# HID2AMI_Deluxe_Rev2_0_0.net
KiCad netlist of a schematic drawn in EAGLE
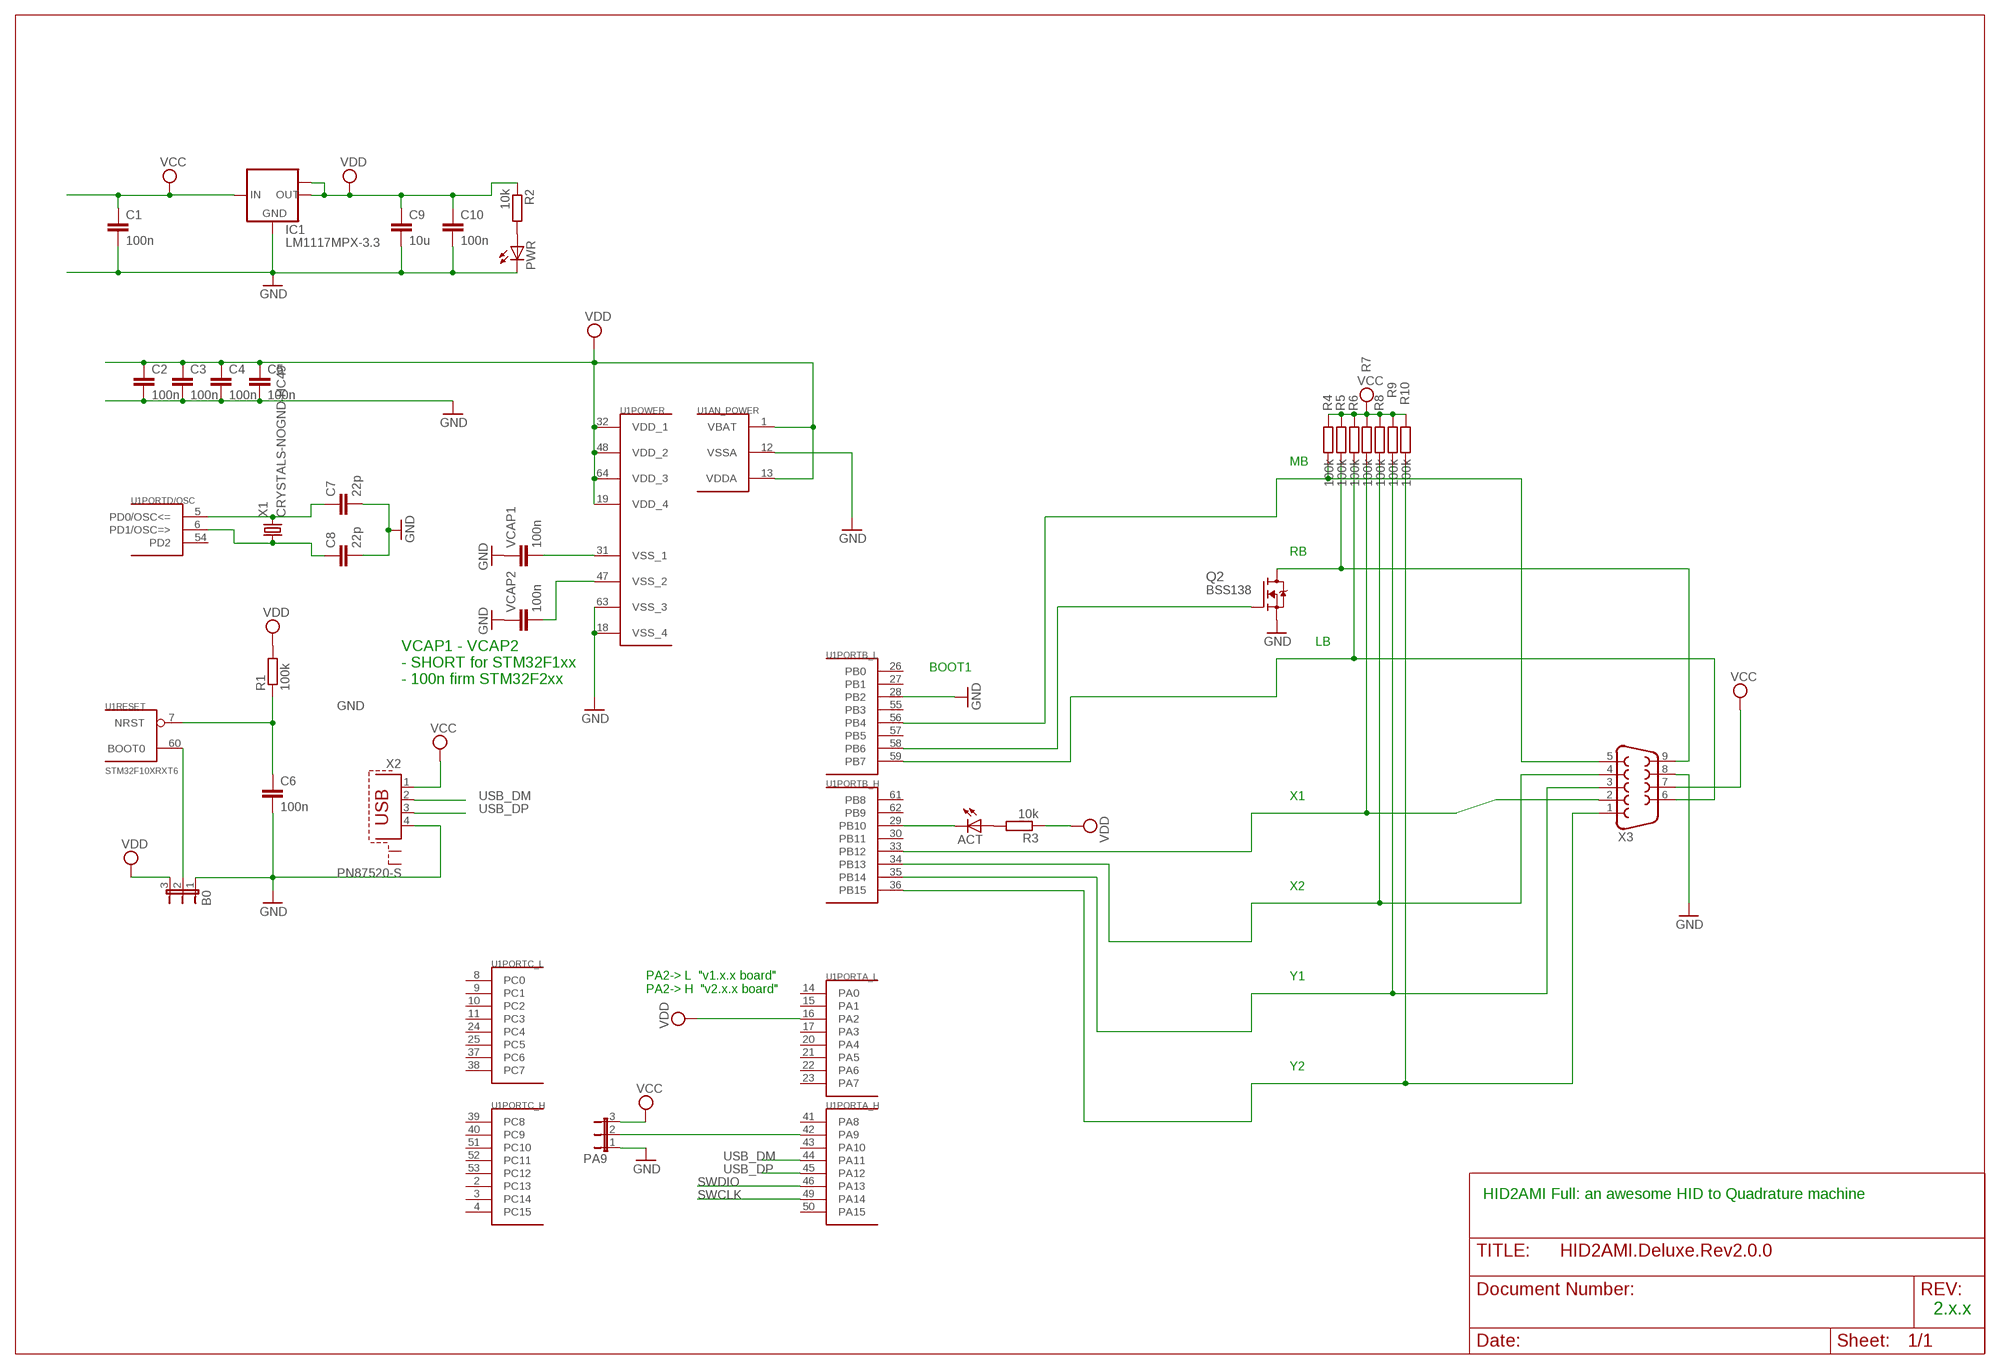
[diagram p0: schematic, sheet 1]

(export (version "E")
  (design (tool "Eeschema 10.0.6"))
  (components
    (comp (ref "ACT")
      (value "LEDSML0805")
      (footprint "eagle-import:SML0805")
      (libsource (lib "eagle-import") (part "LEDSML0805"))
    )
    (comp (ref "B0")
      (value "JP2E")
      (footprint "eagle-import:JP2")
      (libsource (lib "eagle-import") (part "JP2E"))
    )
    (comp (ref "C1")
      (value "100n")
      (footprint "eagle-import:C0805")
      (libsource (lib "eagle-import") (part "C-EUC0805"))
    )
    (comp (ref "C2")
      (value "100n")
      (footprint "eagle-import:C0805")
      (libsource (lib "eagle-import") (part "C-EUC0805"))
    )
    (comp (ref "C3")
      (value "100n")
      (footprint "eagle-import:C0805")
      (libsource (lib "eagle-import") (part "C-EUC0805"))
    )
    (comp (ref "C4")
      (value "100n")
      (footprint "eagle-import:C0805")
      (libsource (lib "eagle-import") (part "C-EUC0805"))
    )
    (comp (ref "C5")
      (value "100n")
      (footprint "eagle-import:C0805")
      (libsource (lib "eagle-import") (part "C-EUC0805"))
    )
    (comp (ref "C6")
      (value "100n")
      (footprint "eagle-import:C0805")
      (libsource (lib "eagle-import") (part "C-EUC0805"))
    )
    (comp (ref "C7")
      (value "22p")
      (footprint "eagle-import:C0805")
      (libsource (lib "eagle-import") (part "C-EUC0805"))
    )
    (comp (ref "C8")
      (value "22p")
      (footprint "eagle-import:C0805")
      (libsource (lib "eagle-import") (part "C-EUC0805"))
    )
    (comp (ref "C9")
      (value "10u")
      (footprint "eagle-import:C0805")
      (libsource (lib "eagle-import") (part "C-EUC0805"))
    )
    (comp (ref "C10")
      (value "100n")
      (footprint "eagle-import:C0805")
      (libsource (lib "eagle-import") (part "C-EUC0805"))
    )
    (comp (ref "IC1")
      (value "LM1117MPX-3.3")
      (footprint "eagle-import:SOT223")
      (libsource (lib "eagle-import") (part "LM1117MPX-3.3"))
    )
    (comp (ref "PA9")
      (value "JP2E")
      (footprint "eagle-import:JP2")
      (libsource (lib "eagle-import") (part "JP2E"))
    )
    (comp (ref "PWR")
      (value "LEDSML0805")
      (footprint "eagle-import:SML0805")
      (libsource (lib "eagle-import") (part "LEDSML0805"))
    )
    (comp (ref "Q2")
      (value "BSS138")
      (footprint "eagle-import:SOT23")
      (fields (field (name "MF") "Fairchild"))
      (libsource (lib "eagle-import") (part "BSS138"))
    )
    (comp (ref "R1")
      (value "100k")
      (footprint "eagle-import:M0805")
      (libsource (lib "eagle-import") (part "R-EU_M0805"))
    )
    (comp (ref "R2")
      (value "10k")
      (footprint "eagle-import:M0805")
      (libsource (lib "eagle-import") (part "R-EU_M0805"))
    )
    (comp (ref "R3")
      (value "10k")
      (footprint "eagle-import:M0805")
      (libsource (lib "eagle-import") (part "R-EU_M0805"))
    )
    (comp (ref "R4")
      (value "100k")
      (footprint "eagle-import:M0805")
      (libsource (lib "eagle-import") (part "R-EU_M0805"))
    )
    (comp (ref "R5")
      (value "100k")
      (footprint "eagle-import:M0805")
      (libsource (lib "eagle-import") (part "R-EU_M0805"))
    )
    (comp (ref "R6")
      (value "100k")
      (footprint "eagle-import:M0805")
      (libsource (lib "eagle-import") (part "R-EU_M0805"))
    )
    (comp (ref "R7")
      (value "100k")
      (footprint "eagle-import:M0805")
      (libsource (lib "eagle-import") (part "R-EU_M0805"))
    )
    (comp (ref "R8")
      (value "100k")
      (footprint "eagle-import:M0805")
      (libsource (lib "eagle-import") (part "R-EU_M0805"))
    )
    (comp (ref "R9")
      (value "100k")
      (footprint "eagle-import:M0805")
      (libsource (lib "eagle-import") (part "R-EU_M0805"))
    )
    (comp (ref "R10")
      (value "100k")
      (footprint "eagle-import:M0805")
      (libsource (lib "eagle-import") (part "R-EU_M0805"))
    )
    (comp (ref "U1")
      (value "STM32F10XRXT6")
      (footprint "eagle-import:TQFP64")
      (libsource (lib "eagle-import") (part "STM32F10XRXT6"))
    )
    (comp (ref "VCAP1")
      (value "100n")
      (footprint "eagle-import:C0805")
      (libsource (lib "eagle-import") (part "C-EUC0805"))
    )
    (comp (ref "VCAP2")
      (value "100n")
      (footprint "eagle-import:C0805")
      (libsource (lib "eagle-import") (part "C-EUC0805"))
    )
    (comp (ref "X1")
      (value "CRYSTALS-NOGND-HC49")
      (footprint "eagle-import:HC49")
      (libsource (lib "eagle-import") (part "CRYSTALS-NOGND-HC49"))
    )
    (comp (ref "X2")
      (value "PN87520-S")
      (footprint "eagle-import:PN87520-S")
      (libsource (lib "eagle-import") (part "PN87520-S"))
    )
    (comp (ref "X3")
      (value "F09HP")
      (footprint "eagle-import:F09HP")
      (libsource (lib "eagle-import") (part "F09HP"))
    )
  )
  (nets
    (net (code "1") (name "/SWCLK") (class "Default")
      (node (ref "U1") (pin "49") (pinfunction "PA14_49") (pintype "bidirectional"))
    )
    (net (code "2") (name "/SWDIO") (class "Default")
      (node (ref "U1") (pin "46") (pinfunction "PA13_46") (pintype "bidirectional"))
    )
    (net (code "3") (name "/USB_DM") (class "Default")
      (node (ref "U1") (pin "44") (pinfunction "PA11_44") (pintype "bidirectional"))
      (node (ref "X2") (pin "2") (pinfunction "2_2") (pintype "passive"))
    )
    (net (code "4") (name "/USB_DP") (class "Default")
      (node (ref "U1") (pin "45") (pinfunction "PA12_45") (pintype "bidirectional"))
      (node (ref "X2") (pin "3") (pinfunction "3_3") (pintype "passive"))
    )
    (net (code "5") (name "GND") (class "Default")
      (node (ref "B0") (pin "1") (pinfunction "1_1") (pintype "passive"))
      (node (ref "C1") (pin "2") (pinfunction "2_2") (pintype "passive"))
      (node (ref "C10") (pin "2") (pinfunction "2_2") (pintype "passive"))
      (node (ref "C2") (pin "2") (pinfunction "2_2") (pintype "passive"))
      (node (ref "C3") (pin "2") (pinfunction "2_2") (pintype "passive"))
      (node (ref "C4") (pin "2") (pinfunction "2_2") (pintype "passive"))
      (node (ref "C5") (pin "2") (pinfunction "2_2") (pintype "passive"))
      (node (ref "C6") (pin "2") (pinfunction "2_2") (pintype "passive"))
      (node (ref "C7") (pin "2") (pinfunction "2_2") (pintype "passive"))
      (node (ref "C8") (pin "2") (pinfunction "2_2") (pintype "passive"))
      (node (ref "C9") (pin "2") (pinfunction "2_2") (pintype "passive"))
      (node (ref "IC1") (pin "1") (pinfunction "GND_1") (pintype "input"))
      (node (ref "PA9") (pin "1") (pinfunction "1_1") (pintype "passive"))
      (node (ref "PWR") (pin "C") (pinfunction "C_C") (pintype "passive"))
      (node (ref "Q2") (pin "2") (pinfunction "S_2") (pintype "passive"))
      (node (ref "U1") (pin "12") (pinfunction "VSSA_12") (pintype "power_in"))
      (node (ref "U1") (pin "18") (pinfunction "VSS_4_18") (pintype "power_in"))
      (node (ref "U1") (pin "28") (pinfunction "PB2_28") (pintype "bidirectional"))
      (node (ref "U1") (pin "63") (pinfunction "VSS_3_63") (pintype "power_in"))
      (node (ref "VCAP1") (pin "1") (pinfunction "1_1") (pintype "passive"))
      (node (ref "VCAP2") (pin "1") (pinfunction "1_1") (pintype "passive"))
      (node (ref "X2") (pin "4") (pinfunction "4_4") (pintype "passive"))
      (node (ref "X3") (pin "8") (pinfunction "8_8") (pintype "passive"))
    )
    (net (code "6") (name "Net-(ACT-PadA)") (class "Default")
      (node (ref "ACT") (pin "A") (pinfunction "A_A") (pintype "passive"))
      (node (ref "R3") (pin "2") (pinfunction "2_2") (pintype "passive"))
    )
    (net (code "7") (name "Net-(PWR-PadA)") (class "Default")
      (node (ref "PWR") (pin "A") (pinfunction "A_A") (pintype "passive"))
      (node (ref "R2") (pin "2") (pinfunction "2_2") (pintype "passive"))
    )
    (net (code "8") (name "Net-(Q2-D)") (class "Default")
      (node (ref "Q2") (pin "3") (pinfunction "D_3") (pintype "passive"))
      (node (ref "R5") (pin "2") (pinfunction "2_2") (pintype "passive"))
      (node (ref "X3") (pin "9") (pinfunction "9_9") (pintype "passive"))
    )
    (net (code "9") (name "Net-(Q2-G)") (class "Default")
      (node (ref "Q2") (pin "1") (pinfunction "G_1") (pintype "passive"))
      (node (ref "U1") (pin "58") (pinfunction "PB6_58") (pintype "bidirectional"))
    )
    (net (code "10") (name "Net-(U1B-PA9)") (class "Default")
      (node (ref "PA9") (pin "2") (pinfunction "2_2") (pintype "passive"))
      (node (ref "U1") (pin "42") (pinfunction "PA9_42") (pintype "bidirectional"))
    )
    (net (code "11") (name "Net-(U1D-PB10)") (class "Default")
      (node (ref "ACT") (pin "C") (pinfunction "C_C") (pintype "passive"))
      (node (ref "U1") (pin "29") (pinfunction "PB10_29") (pintype "bidirectional"))
    )
    (net (code "12") (name "Net-(U1D-PB12)") (class "Default")
      (node (ref "R7") (pin "2") (pinfunction "2_2") (pintype "passive"))
      (node (ref "U1") (pin "33") (pinfunction "PB12_33") (pintype "bidirectional"))
      (node (ref "X3") (pin "2") (pinfunction "2_2") (pintype "passive"))
    )
    (net (code "13") (name "Net-(U1D-PB13)") (class "Default")
      (node (ref "R8") (pin "2") (pinfunction "2_2") (pintype "passive"))
      (node (ref "U1") (pin "34") (pinfunction "PB13_34") (pintype "bidirectional"))
      (node (ref "X3") (pin "4") (pinfunction "4_4") (pintype "passive"))
    )
    (net (code "14") (name "Net-(U1D-PB14)") (class "Default")
      (node (ref "R9") (pin "2") (pinfunction "2_2") (pintype "passive"))
      (node (ref "U1") (pin "35") (pinfunction "PB14_35") (pintype "bidirectional"))
      (node (ref "X3") (pin "3") (pinfunction "3_3") (pintype "passive"))
    )
    (net (code "15") (name "Net-(U1D-PB15)") (class "Default")
      (node (ref "R10") (pin "2") (pinfunction "2_2") (pintype "passive"))
      (node (ref "U1") (pin "36") (pinfunction "PB15_36") (pintype "bidirectional"))
      (node (ref "X3") (pin "1") (pinfunction "1_1") (pintype "passive"))
    )
    (net (code "16") (name "Net-(U1E-PB4)") (class "Default")
      (node (ref "R4") (pin "2") (pinfunction "2_2") (pintype "passive"))
      (node (ref "U1") (pin "56") (pinfunction "PB4_56") (pintype "bidirectional"))
      (node (ref "X3") (pin "5") (pinfunction "5_5") (pintype "passive"))
    )
    (net (code "17") (name "Net-(U1E-PB7)") (class "Default")
      (node (ref "R6") (pin "2") (pinfunction "2_2") (pintype "passive"))
      (node (ref "U1") (pin "59") (pinfunction "PB7_59") (pintype "bidirectional"))
      (node (ref "X3") (pin "6") (pinfunction "6_6") (pintype "passive"))
    )
    (net (code "18") (name "Net-(U1H-PD0{slash}OSC<=)") (class "Default")
      (node (ref "C7") (pin "1") (pinfunction "1_1") (pintype "passive"))
      (node (ref "U1") (pin "5") (pinfunction "PD0/OSC<=_5") (pintype "bidirectional"))
      (node (ref "X1") (pin "2") (pinfunction "2_2") (pintype "passive"))
    )
    (net (code "19") (name "Net-(U1H-PD1{slash}OSC=>)") (class "Default")
      (node (ref "C8") (pin "1") (pinfunction "1_1") (pintype "passive"))
      (node (ref "U1") (pin "6") (pinfunction "PD1/OSC=>_6") (pintype "bidirectional"))
      (node (ref "X1") (pin "1") (pinfunction "1_1") (pintype "passive"))
    )
    (net (code "20") (name "Net-(U1I-VSS_1)") (class "Default")
      (node (ref "U1") (pin "31") (pinfunction "VSS_1_31") (pintype "power_in"))
      (node (ref "VCAP1") (pin "2") (pinfunction "2_2") (pintype "passive"))
    )
    (net (code "21") (name "Net-(U1I-VSS_2)") (class "Default")
      (node (ref "U1") (pin "47") (pinfunction "VSS_2_47") (pintype "power_in"))
      (node (ref "VCAP2") (pin "2") (pinfunction "2_2") (pintype "passive"))
    )
    (net (code "22") (name "Net-(U1J-BOOT0)") (class "Default")
      (node (ref "B0") (pin "2") (pinfunction "2_2") (pintype "passive"))
      (node (ref "U1") (pin "60") (pinfunction "BOOT0_60") (pintype "input"))
    )
    (net (code "23") (name "Net-(U1J-NRST)") (class "Default")
      (node (ref "C6") (pin "1") (pinfunction "1_1") (pintype "passive"))
      (node (ref "R1") (pin "1") (pinfunction "1_1") (pintype "passive"))
      (node (ref "U1") (pin "7") (pinfunction "NRST_7") (pintype "input"))
    )
    (net (code "24") (name "VCC") (class "Default")
      (node (ref "C1") (pin "1") (pinfunction "1_1") (pintype "passive"))
      (node (ref "IC1") (pin "3") (pinfunction "IN_3") (pintype "input"))
      (node (ref "PA9") (pin "3") (pinfunction "3_3") (pintype "passive"))
      (node (ref "R10") (pin "1") (pinfunction "1_1") (pintype "passive"))
      (node (ref "R4") (pin "1") (pinfunction "1_1") (pintype "passive"))
      (node (ref "R5") (pin "1") (pinfunction "1_1") (pintype "passive"))
      (node (ref "R6") (pin "1") (pinfunction "1_1") (pintype "passive"))
      (node (ref "R7") (pin "1") (pinfunction "1_1") (pintype "passive"))
      (node (ref "R8") (pin "1") (pinfunction "1_1") (pintype "passive"))
      (node (ref "R9") (pin "1") (pinfunction "1_1") (pintype "passive"))
      (node (ref "X2") (pin "1") (pinfunction "1_1") (pintype "passive"))
      (node (ref "X3") (pin "7") (pinfunction "7_7") (pintype "passive"))
    )
    (net (code "25") (name "VDD") (class "Default")
      (node (ref "B0") (pin "3") (pinfunction "3_3") (pintype "passive"))
      (node (ref "C10") (pin "1") (pinfunction "1_1") (pintype "passive"))
      (node (ref "C2") (pin "1") (pinfunction "1_1") (pintype "passive"))
      (node (ref "C3") (pin "1") (pinfunction "1_1") (pintype "passive"))
      (node (ref "C4") (pin "1") (pinfunction "1_1") (pintype "passive"))
      (node (ref "C5") (pin "1") (pinfunction "1_1") (pintype "passive"))
      (node (ref "C9") (pin "1") (pinfunction "1_1") (pintype "passive"))
      (node (ref "IC1") (pin "2") (pinfunction "OUT_2") (pintype "passive"))
      (node (ref "IC1") (pin "TAB") (pinfunction "OUT1_TAB") (pintype "passive"))
      (node (ref "R1") (pin "2") (pinfunction "2_2") (pintype "passive"))
      (node (ref "R2") (pin "1") (pinfunction "1_1") (pintype "passive"))
      (node (ref "R3") (pin "1") (pinfunction "1_1") (pintype "passive"))
      (node (ref "U1") (pin "1") (pinfunction "VBAT_1") (pintype "power_in"))
      (node (ref "U1") (pin "13") (pinfunction "VDDA_13") (pintype "power_in"))
      (node (ref "U1") (pin "16") (pinfunction "PA2_16") (pintype "bidirectional"))
      (node (ref "U1") (pin "19") (pinfunction "VDD_4_19") (pintype "power_in"))
      (node (ref "U1") (pin "32") (pinfunction "VDD_1_32") (pintype "power_in"))
      (node (ref "U1") (pin "48") (pinfunction "VDD_2_48") (pintype "power_in"))
      (node (ref "U1") (pin "64") (pinfunction "VDD_3_64") (pintype "power_in"))
    )
    (net (code "26") (name "unconnected-(U1B-PA8-Pad41)") (class "Default")
      (node (ref "U1") (pin "41") (pinfunction "PA8_41") (pintype "bidirectional"))
    )
    (net (code "27") (name "unconnected-(U1B-PA10-Pad43)") (class "Default")
      (node (ref "U1") (pin "43") (pinfunction "PA10_43") (pintype "bidirectional"))
    )
    (net (code "28") (name "unconnected-(U1B-PA15-Pad50)") (class "Default")
      (node (ref "U1") (pin "50") (pinfunction "PA15_50") (pintype "bidirectional"))
    )
    (net (code "29") (name "unconnected-(U1C-PA0-Pad14)") (class "Default")
      (node (ref "U1") (pin "14") (pinfunction "PA0_14") (pintype "bidirectional"))
    )
    (net (code "30") (name "unconnected-(U1C-PA1-Pad15)") (class "Default")
      (node (ref "U1") (pin "15") (pinfunction "PA1_15") (pintype "bidirectional"))
    )
    (net (code "31") (name "unconnected-(U1C-PA3-Pad17)") (class "Default")
      (node (ref "U1") (pin "17") (pinfunction "PA3_17") (pintype "bidirectional"))
    )
    (net (code "32") (name "unconnected-(U1C-PA4-Pad20)") (class "Default")
      (node (ref "U1") (pin "20") (pinfunction "PA4_20") (pintype "bidirectional"))
    )
    (net (code "33") (name "unconnected-(U1C-PA5-Pad21)") (class "Default")
      (node (ref "U1") (pin "21") (pinfunction "PA5_21") (pintype "bidirectional"))
    )
    (net (code "34") (name "unconnected-(U1C-PA6-Pad22)") (class "Default")
      (node (ref "U1") (pin "22") (pinfunction "PA6_22") (pintype "bidirectional"))
    )
    (net (code "35") (name "unconnected-(U1C-PA7-Pad23)") (class "Default")
      (node (ref "U1") (pin "23") (pinfunction "PA7_23") (pintype "bidirectional"))
    )
    (net (code "36") (name "unconnected-(U1D-PB8-Pad61)") (class "Default")
      (node (ref "U1") (pin "61") (pinfunction "PB8_61") (pintype "bidirectional"))
    )
    (net (code "37") (name "unconnected-(U1D-PB9-Pad62)") (class "Default")
      (node (ref "U1") (pin "62") (pinfunction "PB9_62") (pintype "bidirectional"))
    )
    (net (code "38") (name "unconnected-(U1D-PB11-Pad30)") (class "Default")
      (node (ref "U1") (pin "30") (pinfunction "PB11_30") (pintype "bidirectional"))
    )
    (net (code "39") (name "unconnected-(U1E-PB0-Pad26)") (class "Default")
      (node (ref "U1") (pin "26") (pinfunction "PB0_26") (pintype "bidirectional"))
    )
    (net (code "40") (name "unconnected-(U1E-PB1-Pad27)") (class "Default")
      (node (ref "U1") (pin "27") (pinfunction "PB1_27") (pintype "bidirectional"))
    )
    (net (code "41") (name "unconnected-(U1E-PB3-Pad55)") (class "Default")
      (node (ref "U1") (pin "55") (pinfunction "PB3_55") (pintype "bidirectional"))
    )
    (net (code "42") (name "unconnected-(U1E-PB5-Pad57)") (class "Default")
      (node (ref "U1") (pin "57") (pinfunction "PB5_57") (pintype "bidirectional"))
    )
    (net (code "43") (name "unconnected-(U1F-PC8-Pad39)") (class "Default")
      (node (ref "U1") (pin "39") (pinfunction "PC8_39") (pintype "bidirectional"))
    )
    (net (code "44") (name "unconnected-(U1F-PC9-Pad40)") (class "Default")
      (node (ref "U1") (pin "40") (pinfunction "PC9_40") (pintype "bidirectional"))
    )
    (net (code "45") (name "unconnected-(U1F-PC10-Pad51)") (class "Default")
      (node (ref "U1") (pin "51") (pinfunction "PC10_51") (pintype "bidirectional"))
    )
    (net (code "46") (name "unconnected-(U1F-PC11-Pad52)") (class "Default")
      (node (ref "U1") (pin "52") (pinfunction "PC11_52") (pintype "bidirectional"))
    )
    (net (code "47") (name "unconnected-(U1F-PC12-Pad53)") (class "Default")
      (node (ref "U1") (pin "53") (pinfunction "PC12_53") (pintype "bidirectional"))
    )
    (net (code "48") (name "unconnected-(U1F-PC13-Pad2)") (class "Default")
      (node (ref "U1") (pin "2") (pinfunction "PC13_2") (pintype "bidirectional"))
    )
    (net (code "49") (name "unconnected-(U1F-PC14-Pad3)") (class "Default")
      (node (ref "U1") (pin "3") (pinfunction "PC14_3") (pintype "bidirectional"))
    )
    (net (code "50") (name "unconnected-(U1F-PC15-Pad4)") (class "Default")
      (node (ref "U1") (pin "4") (pinfunction "PC15_4") (pintype "bidirectional"))
    )
    (net (code "51") (name "unconnected-(U1G-PC0-Pad8)") (class "Default")
      (node (ref "U1") (pin "8") (pinfunction "PC0_8") (pintype "bidirectional"))
    )
    (net (code "52") (name "unconnected-(U1G-PC1-Pad9)") (class "Default")
      (node (ref "U1") (pin "9") (pinfunction "PC1_9") (pintype "bidirectional"))
    )
    (net (code "53") (name "unconnected-(U1G-PC2-Pad10)") (class "Default")
      (node (ref "U1") (pin "10") (pinfunction "PC2_10") (pintype "bidirectional"))
    )
    (net (code "54") (name "unconnected-(U1G-PC3-Pad11)") (class "Default")
      (node (ref "U1") (pin "11") (pinfunction "PC3_11") (pintype "bidirectional"))
    )
    (net (code "55") (name "unconnected-(U1G-PC4-Pad24)") (class "Default")
      (node (ref "U1") (pin "24") (pinfunction "PC4_24") (pintype "bidirectional"))
    )
    (net (code "56") (name "unconnected-(U1G-PC5-Pad25)") (class "Default")
      (node (ref "U1") (pin "25") (pinfunction "PC5_25") (pintype "bidirectional"))
    )
    (net (code "57") (name "unconnected-(U1G-PC6-Pad37)") (class "Default")
      (node (ref "U1") (pin "37") (pinfunction "PC6_37") (pintype "bidirectional"))
    )
    (net (code "58") (name "unconnected-(U1G-PC7-Pad38)") (class "Default")
      (node (ref "U1") (pin "38") (pinfunction "PC7_38") (pintype "bidirectional"))
    )
    (net (code "59") (name "unconnected-(U1H-PD2-Pad54)") (class "Default")
      (node (ref "U1") (pin "54") (pinfunction "PD2_54") (pintype "bidirectional"))
    )
    (net (code "60") (name "unconnected-(X2-PadS1)") (class "Default")
      (node (ref "X2") (pin "S1") (pinfunction "S1_S1") (pintype "passive"))
    )
    (net (code "61") (name "unconnected-(X2-PadS2)") (class "Default")
      (node (ref "X2") (pin "S2") (pinfunction "S2_S2") (pintype "passive"))
    )
  )
)
